# PG_N_Indicator.net
KiCad netlist of a schematic drawn in Altium Designer
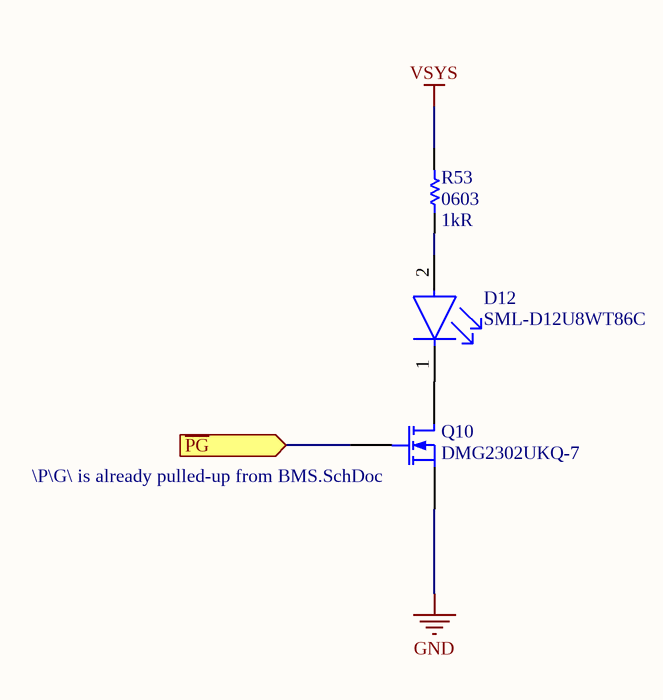
[diagram p0: PG_N_Indicator.SchDoc]

(export (version "E")
  (design (tool "Eeschema 10.0.6"))
  (components
    (comp (ref "D12")
      (value "SML-D12U8WT86C")
      (footprint "FP-SML-D12-MFG")
      (description "LED RED 1608 SMD")
      (fields
        (field (name "OCTOPART") "https://octopart.com/sml-d12u8wt86c-rohm-77740214")
        (field (name "MANUFACTURER") "Rohm")
      )
      (libsource (lib "Altium Content Vault") (part "8706943c75ba83719d021d2fdc84c58"))
    )
    (comp (ref "Q10")
      (value "~")
      (footprint "*SOT23")
      (description "Mosfet, N-ch, 20V, 2.8A, SOT-23 Rohs Compliant: Yes")
      (fields (field (name "MANUFACTURER") "Diodes") (field (name "MANUFACTURER PART NUMBER") "DMG2302UKQ-7"))
      (libsource (lib "Wally_BMS") (part "DMG2302UK-7"))
    )
    (comp (ref "R53")
      (value "Resistor 0603")
      (footprint "RES0603")
      (description "Res Thick Film 0603 1K Ohm 1% 0.25W(1/4W) ±100ppm/°C Epoxy Resin Pad SMD Automotive T/R")
      (fields
        (field (name "PACKAGE / CASE") "0603")
        (field (name "MANUFACTURER") "Rohm")
        (field (name "MANUFACTURER PART NUMBER") "ESR03EZPF1001")
        (field (name "RESISTANCE") "1kR")
      )
      (libsource (lib "Wally_BMS") (part "Resistor 0603"))
    )
  )
  (nets
    (net (code "1") (name "/~{PG}") (class "Default")
      (node (ref "Q10") (pin "1") (pinfunction "G_1") (pintype "passive"))
    )
    (net (code "2") (name "GND") (class "Default")
      (node (ref "Q10") (pin "2") (pinfunction "S_2") (pintype "passive"))
    )
    (net (code "3") (name "Net-(D12-A)") (class "Default")
      (node (ref "D12") (pin "2") (pinfunction "A_2") (pintype "passive"))
      (node (ref "R53") (pin "1") (pinfunction "1_1") (pintype "passive"))
    )
    (net (code "4") (name "Net-(D12-C)") (class "Default")
      (node (ref "D12") (pin "1") (pinfunction "C_1") (pintype "passive"))
      (node (ref "Q10") (pin "3") (pinfunction "D_3") (pintype "passive"))
    )
    (net (code "5") (name "VSYS") (class "Default")
      (node (ref "R53") (pin "2") (pinfunction "2_2") (pintype "passive"))
    )
  )
)
